# Jacdac_Pressure_Sensor-RevA.net
KiCad netlist of a schematic drawn in EAGLE
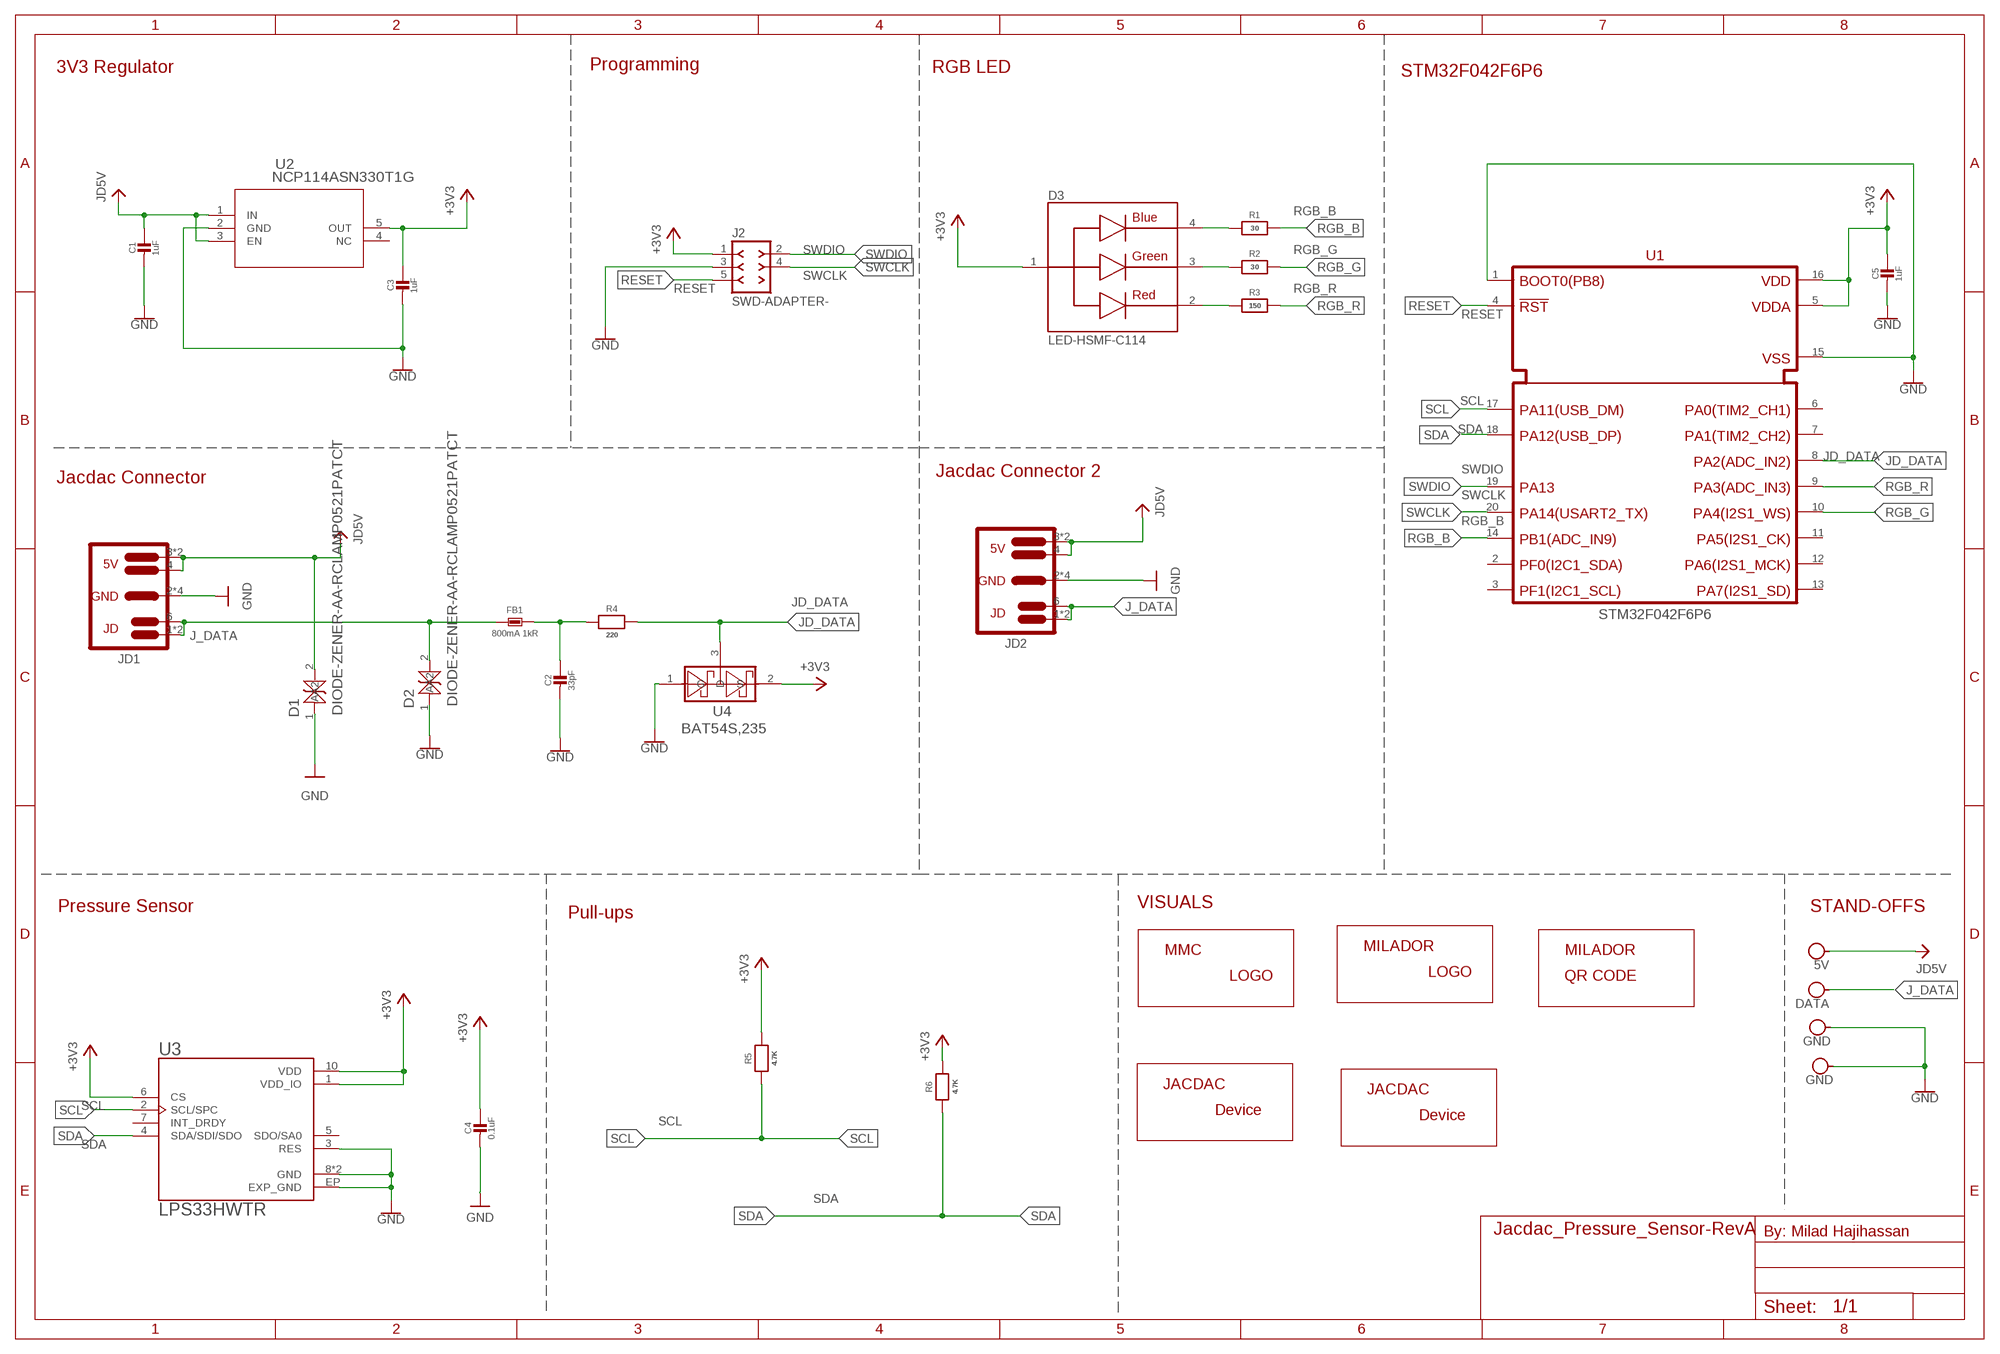
[diagram p0: schematic, sheet 1]

(export (version "E")
  (design (tool "Eeschema 10.0.6"))
  (components
    (comp (ref "C1")
      (value "1uF")
      (footprint "eagle-import:0603-NO")
      (libsource (lib "eagle-import") (part "CAP_CERAMIC-0603-NO"))
    )
    (comp (ref "C2")
      (value "33pF")
      (footprint "eagle-import:0603")
      (libsource (lib "eagle-import") (part "CAP_CERAMIC-0603"))
    )
    (comp (ref "C3")
      (value "1uF")
      (footprint "eagle-import:0603-NO")
      (libsource (lib "eagle-import") (part "CAP_CERAMIC-0603-NO"))
    )
    (comp (ref "C4")
      (value "0.1uF")
      (footprint "eagle-import:0603-NO")
      (libsource (lib "eagle-import") (part "CAP_CERAMIC-0603-NO"))
    )
    (comp (ref "C5")
      (value "1uF")
      (footprint "eagle-import:0603")
      (libsource (lib "eagle-import") (part "CAP_CERAMIC-0603"))
    )
    (comp (ref "D1")
      (value "DIODE-ZENER-AA-RCLAMP0521PATCT")
      (footprint "eagle-import:DIODE-ZENER-0402")
      (fields
        (field (name "MANUFACTURER_PART_NUMBER") "RCLAMP0521PATCT")
        (field (name "COPYRIGHT") "Copyright (C) 2021 Ultra Librarian. All rights reserved.")
      )
      (libsource (lib "eagle-import") (part "DIODE-ZENER-AA-RCLAMP0521PATCT"))
    )
    (comp (ref "D2")
      (value "DIODE-ZENER-AA-RCLAMP0521PATCT")
      (footprint "eagle-import:DIODE-ZENER-0402")
      (fields
        (field (name "MANUFACTURER_PART_NUMBER") "RCLAMP0521PATCT")
        (field (name "COPYRIGHT") "Copyright (C) 2021 Ultra Librarian. All rights reserved.")
      )
      (libsource (lib "eagle-import") (part "DIODE-ZENER-AA-RCLAMP0521PATCT"))
    )
    (comp (ref "D3")
      (value "LED-HSMF-C114")
      (footprint "eagle-import:DIOSC160X150X35-4N")
      (fields (field (name "MF") "Broadcom Limited") (field (name "MP") "HSMF-C114"))
      (libsource (lib "eagle-import") (part "LED-HSMF-C114"))
    )
    (comp (ref "FB1")
      (value "800mA 1kR")
      (footprint "eagle-import:0603-NO")
      (libsource (lib "eagle-import") (part "FERRITE-BEAD-0603-NO"))
    )
    (comp (ref "J2")
      (value "SWD-ADAPTER-")
      (footprint "eagle-import:SWD-ADAPTER")
      (libsource (lib "eagle-import") (part "SWD-ADAPTER-"))
    )
    (comp (ref "J3")
      (value "5V")
      (footprint "eagle-import:M3-HOLE-PWR-OUTL")
      (libsource (lib "eagle-import") (part "JACDAC-M3-PWR-OUTL"))
    )
    (comp (ref "J4")
      (value "DATA")
      (footprint "eagle-import:M3-HOLE-DATA-NOTCH")
      (libsource (lib "eagle-import") (part "JACDAC-M3-DATA-NOTCH"))
    )
    (comp (ref "J5")
      (value "GND")
      (footprint "eagle-import:M3-HOLE-GND")
      (libsource (lib "eagle-import") (part "JACDAC-M3-GND"))
    )
    (comp (ref "J6")
      (value "GND")
      (footprint "eagle-import:M3-HOLE-GND")
      (libsource (lib "eagle-import") (part "JACDAC-M3-GND"))
    )
    (comp (ref "JD1")
      (value "JACDAC-EDGE-OUTIE")
      (footprint "eagle-import:JD-EDGE-OUTIE")
      (libsource (lib "eagle-import") (part "JACDAC-EDGE-OUTIE"))
    )
    (comp (ref "JD2")
      (value "JACDAC-EDGE-OUTIE")
      (footprint "eagle-import:JD-EDGE-OUTIE")
      (libsource (lib "eagle-import") (part "JACDAC-EDGE-OUTIE"))
    )
    (comp (ref "LABEL_JACDAC_PS")
      (value "MILADOR-JACDAC-DEVICE-PS")
      (footprint "eagle-import:JACDAC-PRESSURE-SENSOR")
      (libsource (lib "eagle-import") (part "MILADOR-JACDAC-DEVICE-PS"))
    )
    (comp (ref "LABEL_LPS33HW")
      (value "MILADOR-JACDAC-DEVICE-LPS33HW")
      (footprint "eagle-import:JACDAC-LPS33HW")
      (libsource (lib "eagle-import") (part "MILADOR-JACDAC-DEVICE-LPS33HW"))
    )
    (comp (ref "LABEL_MILADOR")
      (value "MILADOR-LOGO-")
      (footprint "eagle-import:MILADOR_LOGO1")
      (libsource (lib "eagle-import") (part "MILADOR-LOGO-"))
    )
    (comp (ref "LABEL_QR_CODE")
      (value "MILADOR-QR-CODE-JACDAC-GITHUB-PS")
      (footprint "eagle-import:MILADOR_QR_JACDAC_PS")
      (libsource (lib "eagle-import") (part "MILADOR-QR-CODE-JACDAC-GITHUB-PS"))
    )
    (comp (ref "MMC_LOGO")
      (value "MMC_LOGO-XSM")
      (footprint "eagle-import:MMC_X-SMALL_LOGO")
      (libsource (lib "eagle-import") (part "MMC_LOGO-XSM"))
    )
    (comp (ref "R1")
      (value "30")
      (footprint "eagle-import:0603")
      (libsource (lib "eagle-import") (part "RESISTOR-0603"))
    )
    (comp (ref "R2")
      (value "30")
      (footprint "eagle-import:0603")
      (libsource (lib "eagle-import") (part "RESISTOR-0603"))
    )
    (comp (ref "R3")
      (value "150")
      (footprint "eagle-import:0603")
      (libsource (lib "eagle-import") (part "RESISTOR-0603"))
    )
    (comp (ref "R4")
      (value "220")
      (footprint "eagle-import:0603")
      (libsource (lib "eagle-import") (part "RESISTOR-0603"))
    )
    (comp (ref "R5")
      (value "4.7K")
      (footprint "eagle-import:0603")
      (libsource (lib "eagle-import") (part "RESISTOR-0603"))
    )
    (comp (ref "R6")
      (value "4.7K")
      (footprint "eagle-import:0603")
      (libsource (lib "eagle-import") (part "RESISTOR-0603"))
    )
    (comp (ref "U1")
      (value "STM32F042F6P6")
      (footprint "eagle-import:TSSOP20")
      (libsource (lib "eagle-import") (part "STM32F042F6P6"))
    )
    (comp (ref "U2")
      (value "NCP114ASN330T1G")
      (footprint "eagle-import:TSOP-5_ONS")
      (fields (field (name "COPYRIGHT") "Copyright (C) 2021 Ultra Librarian. All rights reserved."))
      (libsource (lib "eagle-import") (part "NCP114ASN330T1G"))
    )
    (comp (ref "U3")
      (value "LPS33HWTR")
      (footprint "eagle-import:PQFN60P330X330X290-11N")
      (fields (field (name "DIGI-KEY_PART_NUMBER") "497-17590-1-ND") (field (name "MF") "STMicroelectronics"))
      (libsource (lib "eagle-import") (part "LPS33HWTR"))
    )
    (comp (ref "U4")
      (value "BAT54S,235")
      (footprint "eagle-import:SOT23-3")
      (fields (field (name "MF") "Diodes") (field (name "MP") "BSS138-7-F"))
      (libsource (lib "eagle-import") (part "BAT54S,235"))
    )
  )
  (nets
    (net (code "1") (name "+3V3") (class "Default")
      (node (ref "C3") (pin "1") (pinfunction "1_1") (pintype "passive"))
      (node (ref "C4") (pin "1") (pinfunction "1_1") (pintype "passive"))
      (node (ref "C5") (pin "1") (pinfunction "1_1") (pintype "passive"))
      (node (ref "D3") (pin "1") (pinfunction "1_1") (pintype "passive"))
      (node (ref "J2") (pin "1") (pinfunction "VCC_1_1") (pintype "passive"))
      (node (ref "R5") (pin "2") (pinfunction "2_2") (pintype "passive"))
      (node (ref "R6") (pin "2") (pinfunction "2_2") (pintype "passive"))
      (node (ref "U1") (pin "16") (pinfunction "VDD_16") (pintype "input"))
      (node (ref "U1") (pin "5") (pinfunction "VDDA_5") (pintype "input"))
      (node (ref "U2") (pin "5") (pinfunction "OUT_5") (pintype "power_in"))
      (node (ref "U3") (pin "1") (pinfunction "VDD_IO_1") (pintype "power_in"))
      (node (ref "U3") (pin "10") (pinfunction "VDD_10") (pintype "power_in"))
      (node (ref "U3") (pin "6") (pinfunction "CS_6") (pintype "bidirectional"))
      (node (ref "U4") (pin "2") (pinfunction "S_2") (pintype "passive"))
    )
    (net (code "2") (name "GND") (class "Default")
      (node (ref "C1") (pin "2") (pinfunction "2_2") (pintype "passive"))
      (node (ref "C2") (pin "2") (pinfunction "2_2") (pintype "passive"))
      (node (ref "C3") (pin "2") (pinfunction "2_2") (pintype "passive"))
      (node (ref "C4") (pin "2") (pinfunction "2_2") (pintype "passive"))
      (node (ref "C5") (pin "2") (pinfunction "2_2") (pintype "passive"))
      (node (ref "D1") (pin "1") (pinfunction "A_1") (pintype "passive"))
      (node (ref "D2") (pin "1") (pinfunction "A_1") (pintype "passive"))
      (node (ref "J2") (pin "3") (pinfunction "GND_3_3") (pintype "passive"))
      (node (ref "J5") (pin "H") (pinfunction "P$1_H") (pintype "bidirectional"))
      (node (ref "J6") (pin "H") (pinfunction "P$1_H") (pintype "bidirectional"))
      (node (ref "JD1") (pin "2") (pinfunction "1_2") (pintype "power_in"))
      (node (ref "JD1") (pin "5") (pinfunction "1_5") (pintype "power_in"))
      (node (ref "JD1") (pin "P$2") (pinfunction "1_P$2") (pintype "power_in"))
      (node (ref "JD1") (pin "P$4") (pinfunction "1_P$4") (pintype "power_in"))
      (node (ref "JD2") (pin "2") (pinfunction "1_2") (pintype "power_in"))
      (node (ref "JD2") (pin "5") (pinfunction "1_5") (pintype "power_in"))
      (node (ref "JD2") (pin "P$2") (pinfunction "1_P$2") (pintype "power_in"))
      (node (ref "JD2") (pin "P$4") (pinfunction "1_P$4") (pintype "power_in"))
      (node (ref "U1") (pin "1") (pinfunction "BOOT0_1") (pintype "input"))
      (node (ref "U1") (pin "15") (pinfunction "VSS_15") (pintype "input"))
      (node (ref "U2") (pin "2") (pinfunction "GND_2") (pintype "passive"))
      (node (ref "U3") (pin "3") (pinfunction "RES_3") (pintype "passive"))
      (node (ref "U3") (pin "8") (pinfunction "GND_8") (pintype "power_in"))
      (node (ref "U3") (pin "9") (pinfunction "GND_9") (pintype "power_in"))
      (node (ref "U3") (pin "EP") (pinfunction "EXP_GND_EP") (pintype "power_in"))
      (node (ref "U4") (pin "1") (pinfunction "G_1") (pintype "passive"))
    )
    (net (code "3") (name "JD5V") (class "Default")
      (node (ref "C1") (pin "1") (pinfunction "1_1") (pintype "passive"))
      (node (ref "D1") (pin "2") (pinfunction "A2_2") (pintype "passive"))
      (node (ref "J3") (pin "H") (pinfunction "P$1_H") (pintype "bidirectional"))
      (node (ref "JD1") (pin "3") (pinfunction "3_3") (pintype "power_in"))
      (node (ref "JD1") (pin "4") (pinfunction "4_4") (pintype "power_in"))
      (node (ref "JD1") (pin "P$1") (pinfunction "3_P$1") (pintype "power_in"))
      (node (ref "JD2") (pin "3") (pinfunction "3_3") (pintype "power_in"))
      (node (ref "JD2") (pin "4") (pinfunction "4_4") (pintype "power_in"))
      (node (ref "JD2") (pin "P$1") (pinfunction "3_P$1") (pintype "power_in"))
      (node (ref "U2") (pin "1") (pinfunction "IN_1") (pintype "input"))
      (node (ref "U2") (pin "3") (pinfunction "EN_3") (pintype "passive"))
    )
    (net (code "4") (name "JD_DATA") (class "Default")
      (node (ref "R4") (pin "2") (pinfunction "2_2") (pintype "passive"))
      (node (ref "U1") (pin "8") (pinfunction "PA2_8") (pintype "bidirectional"))
      (node (ref "U4") (pin "3") (pinfunction "D_3") (pintype "passive"))
    )
    (net (code "5") (name "J_DATA") (class "Default")
      (node (ref "D2") (pin "2") (pinfunction "A2_2") (pintype "passive"))
      (node (ref "FB1") (pin "2") (pinfunction "2_2") (pintype "passive"))
      (node (ref "J4") (pin "H") (pinfunction "P$1_H") (pintype "bidirectional"))
      (node (ref "JD1") (pin "1") (pinfunction "2_1") (pintype "bidirectional"))
      (node (ref "JD1") (pin "6") (pinfunction "6_6") (pintype "bidirectional"))
      (node (ref "JD1") (pin "P$3") (pinfunction "2_P$3") (pintype "bidirectional"))
      (node (ref "JD2") (pin "1") (pinfunction "2_1") (pintype "bidirectional"))
      (node (ref "JD2") (pin "6") (pinfunction "6_6") (pintype "bidirectional"))
      (node (ref "JD2") (pin "P$3") (pinfunction "2_P$3") (pintype "bidirectional"))
    )
    (net (code "6") (name "Net-(C2-Pad1)") (class "Default")
      (node (ref "C2") (pin "1") (pinfunction "1_1") (pintype "passive"))
      (node (ref "FB1") (pin "1") (pinfunction "1_1") (pintype "passive"))
      (node (ref "R4") (pin "1") (pinfunction "1_1") (pintype "passive"))
    )
    (net (code "7") (name "Net-(D3-Pad2)") (class "Default")
      (node (ref "D3") (pin "2") (pinfunction "2_2") (pintype "passive"))
      (node (ref "R3") (pin "1") (pinfunction "1_1") (pintype "passive"))
    )
    (net (code "8") (name "Net-(D3-Pad3)") (class "Default")
      (node (ref "D3") (pin "3") (pinfunction "3_3") (pintype "passive"))
      (node (ref "R2") (pin "1") (pinfunction "1_1") (pintype "passive"))
    )
    (net (code "9") (name "Net-(D3-Pad4)") (class "Default")
      (node (ref "D3") (pin "4") (pinfunction "4_4") (pintype "passive"))
      (node (ref "R1") (pin "1") (pinfunction "1_1") (pintype "passive"))
    )
    (net (code "10") (name "RESET") (class "Default")
      (node (ref "J2") (pin "5") (pinfunction "RESET_5_5") (pintype "passive"))
      (node (ref "U1") (pin "4") (pinfunction "~{RST}_4") (pintype "input"))
    )
    (net (code "11") (name "RGB_B") (class "Default")
      (node (ref "R1") (pin "2") (pinfunction "2_2") (pintype "passive"))
      (node (ref "U1") (pin "14") (pinfunction "PB1_14") (pintype "bidirectional"))
    )
    (net (code "12") (name "RGB_G") (class "Default")
      (node (ref "R2") (pin "2") (pinfunction "2_2") (pintype "passive"))
      (node (ref "U1") (pin "10") (pinfunction "PA4_10") (pintype "bidirectional"))
    )
    (net (code "13") (name "RGB_R") (class "Default")
      (node (ref "R3") (pin "2") (pinfunction "2_2") (pintype "passive"))
      (node (ref "U1") (pin "9") (pinfunction "PA3_9") (pintype "bidirectional"))
    )
    (net (code "14") (name "SCL") (class "Default")
      (node (ref "R5") (pin "1") (pinfunction "1_1") (pintype "passive"))
      (node (ref "U1") (pin "17") (pinfunction "PA11_17") (pintype "bidirectional"))
      (node (ref "U3") (pin "2") (pinfunction "SCL/SPC_2") (pintype "input"))
    )
    (net (code "15") (name "SDA") (class "Default")
      (node (ref "R6") (pin "1") (pinfunction "1_1") (pintype "passive"))
      (node (ref "U1") (pin "18") (pinfunction "PA12_18") (pintype "bidirectional"))
      (node (ref "U3") (pin "4") (pinfunction "SDA/SDI/SDO_4") (pintype "bidirectional"))
    )
    (net (code "16") (name "SWCLK") (class "Default")
      (node (ref "J2") (pin "4") (pinfunction "SWCLK_4_4") (pintype "passive"))
      (node (ref "U1") (pin "20") (pinfunction "PA14_20") (pintype "bidirectional"))
    )
    (net (code "17") (name "SWDIO") (class "Default")
      (node (ref "J2") (pin "2") (pinfunction "SWDIO_2_2") (pintype "passive"))
      (node (ref "U1") (pin "19") (pinfunction "PA13_19") (pintype "bidirectional"))
    )
    (net (code "18") (name "unconnected-(U1-PA0-Pad6)") (class "Default")
      (node (ref "U1") (pin "6") (pinfunction "PA0_6") (pintype "bidirectional"))
    )
    (net (code "19") (name "unconnected-(U1-PA1-Pad7)") (class "Default")
      (node (ref "U1") (pin "7") (pinfunction "PA1_7") (pintype "bidirectional"))
    )
    (net (code "20") (name "unconnected-(U1-PA5-Pad11)") (class "Default")
      (node (ref "U1") (pin "11") (pinfunction "PA5_11") (pintype "bidirectional"))
    )
    (net (code "21") (name "unconnected-(U1-PA6-Pad12)") (class "Default")
      (node (ref "U1") (pin "12") (pinfunction "PA6_12") (pintype "bidirectional"))
    )
    (net (code "22") (name "unconnected-(U1-PA7-Pad13)") (class "Default")
      (node (ref "U1") (pin "13") (pinfunction "PA7_13") (pintype "bidirectional"))
    )
    (net (code "23") (name "unconnected-(U1-PF0-Pad2)") (class "Default")
      (node (ref "U1") (pin "2") (pinfunction "PF0_2") (pintype "bidirectional"))
    )
    (net (code "24") (name "unconnected-(U1-PF1-Pad3)") (class "Default")
      (node (ref "U1") (pin "3") (pinfunction "PF1_3") (pintype "bidirectional"))
    )
    (net (code "25") (name "unconnected-(U2-NC-Pad4)") (class "Default")
      (node (ref "U2") (pin "4") (pinfunction "NC_4") (pintype "no_connect"))
    )
    (net (code "26") (name "unconnected-(U3-INT_DRDY-Pad7)") (class "Default")
      (node (ref "U3") (pin "7") (pinfunction "INT_DRDY_7") (pintype "bidirectional"))
    )
    (net (code "27") (name "unconnected-(U3-SDO{slash}SA0-Pad5)") (class "Default")
      (node (ref "U3") (pin "5") (pinfunction "SDO/SA0_5") (pintype "output"))
    )
  )
)
